# Display_Roll.net
KiCad netlist of a schematic drawn in Altium Designer
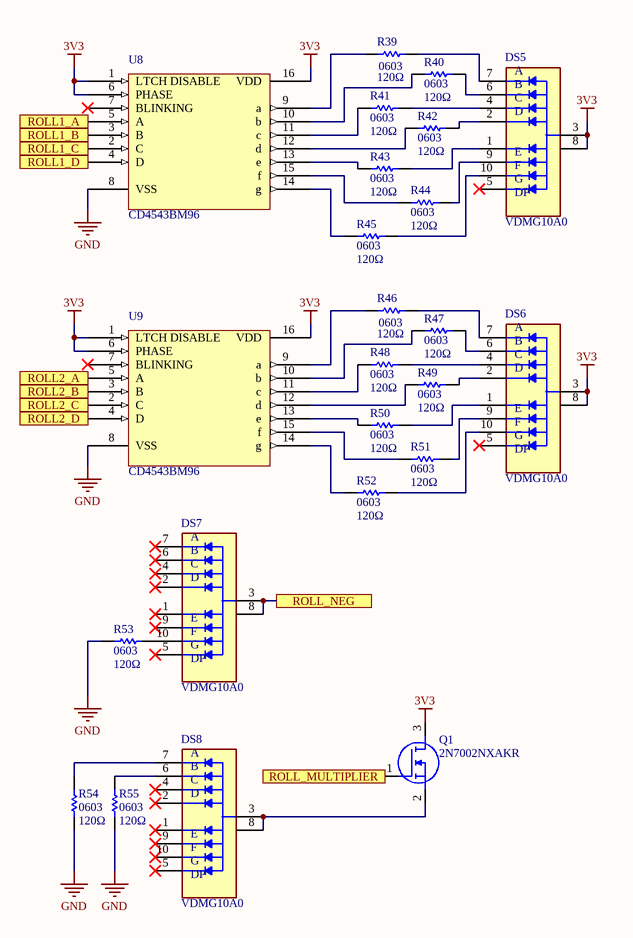
[diagram p0: Display Roll.SchDoc]

(export (version "E")
  (design (tool "Eeschema 10.0.6"))
  (components
    (comp (ref "DS5")
      (value "VDMG10A0")
      (footprint "DISPLAY_VDMG10A0")
      (description "Smart/Normal 7 Seg Numeric LED Display")
      (fields (field (name "MANUFACTURER") "Vishay Semiconductors"))
      (libsource (lib "SKALE_LIB") (part "7 SEG DISPLAY - VDMG10A0"))
    )
    (comp (ref "DS6")
      (value "VDMG10A0")
      (footprint "DISPLAY_VDMG10A0")
      (description "Smart/Normal 7 Seg Numeric LED Display")
      (fields (field (name "MANUFACTURER") "Vishay Semiconductors"))
      (libsource (lib "SKALE_LIB") (part "7 SEG DISPLAY - VDMG10A0"))
    )
    (comp (ref "DS7")
      (value "VDMG10A0")
      (footprint "DISPLAY_VDMG10A0")
      (description "Smart/Normal 7 Seg Numeric LED Display")
      (fields (field (name "MANUFACTURER") "Vishay Semiconductors"))
      (libsource (lib "SKALE_LIB") (part "7 SEG DISPLAY - VDMG10A0"))
    )
    (comp (ref "DS8")
      (value "VDMG10A0")
      (footprint "DISPLAY_VDMG10A0")
      (description "Smart/Normal 7 Seg Numeric LED Display")
      (fields (field (name "MANUFACTURER") "Vishay Semiconductors"))
      (libsource (lib "SKALE_LIB") (part "7 SEG DISPLAY - VDMG10A0"))
    )
    (comp (ref "Q1")
      (value "2N7002NXAKR")
      (footprint "SKALE_LIB:TO-236AB")
      (description "Transistor Mosfet N-ch 60V 0.3A 3-PIN TO-263AB T/r")
      (fields (field (name "MF") "Nexperia USA Inc.") (field (name "MANUFACTURER") "Nexperia"))
      (libsource (lib "SKALE_LIB") (part "MOSFET N-60V-190mA"))
    )
    (comp (ref "R39")
      (value "120Ω")
      (footprint "RES0603")
      (description "RES 120 OHM 5% 1/10W 0603")
      (fields (field (name "PACKAGE/FOOTPRINT") "0603") (field (name "Comment") "RES_120Ω_0603"))
      (libsource (lib "SKALE_LIB") (part "RES_120Ω_0603_5%"))
    )
    (comp (ref "R40")
      (value "120Ω")
      (footprint "RES0603")
      (description "RES 120 OHM 5% 1/10W 0603")
      (fields (field (name "PACKAGE/FOOTPRINT") "0603") (field (name "Comment") "RES_120Ω_0603"))
      (libsource (lib "SKALE_LIB") (part "RES_120Ω_0603_5%"))
    )
    (comp (ref "R41")
      (value "120Ω")
      (footprint "RES0603")
      (description "RES 120 OHM 5% 1/10W 0603")
      (fields (field (name "PACKAGE/FOOTPRINT") "0603") (field (name "Comment") "RES_120Ω_0603"))
      (libsource (lib "SKALE_LIB") (part "RES_120Ω_0603_5%"))
    )
    (comp (ref "R42")
      (value "120Ω")
      (footprint "RES0603")
      (description "RES 120 OHM 5% 1/10W 0603")
      (fields (field (name "PACKAGE/FOOTPRINT") "0603") (field (name "Comment") "RES_120Ω_0603"))
      (libsource (lib "SKALE_LIB") (part "RES_120Ω_0603_5%"))
    )
    (comp (ref "R43")
      (value "120Ω")
      (footprint "RES0603")
      (description "RES 120 OHM 5% 1/10W 0603")
      (fields (field (name "PACKAGE/FOOTPRINT") "0603") (field (name "Comment") "RES_120Ω_0603"))
      (libsource (lib "SKALE_LIB") (part "RES_120Ω_0603_5%"))
    )
    (comp (ref "R44")
      (value "120Ω")
      (footprint "RES0603")
      (description "RES 120 OHM 5% 1/10W 0603")
      (fields (field (name "PACKAGE/FOOTPRINT") "0603") (field (name "Comment") "RES_120Ω_0603"))
      (libsource (lib "SKALE_LIB") (part "RES_120Ω_0603_5%"))
    )
    (comp (ref "R45")
      (value "120Ω")
      (footprint "RES0603")
      (description "RES 120 OHM 5% 1/10W 0603")
      (fields (field (name "PACKAGE/FOOTPRINT") "0603") (field (name "Comment") "RES_120Ω_0603"))
      (libsource (lib "SKALE_LIB") (part "RES_120Ω_0603_5%"))
    )
    (comp (ref "R46")
      (value "120Ω")
      (footprint "RES0603")
      (description "RES 120 OHM 5% 1/10W 0603")
      (fields (field (name "PACKAGE/FOOTPRINT") "0603") (field (name "Comment") "RES_120Ω_0603"))
      (libsource (lib "SKALE_LIB") (part "RES_120Ω_0603_5%"))
    )
    (comp (ref "R47")
      (value "120Ω")
      (footprint "RES0603")
      (description "RES 120 OHM 5% 1/10W 0603")
      (fields (field (name "PACKAGE/FOOTPRINT") "0603") (field (name "Comment") "RES_120Ω_0603"))
      (libsource (lib "SKALE_LIB") (part "RES_120Ω_0603_5%"))
    )
    (comp (ref "R48")
      (value "120Ω")
      (footprint "RES0603")
      (description "RES 120 OHM 5% 1/10W 0603")
      (fields (field (name "PACKAGE/FOOTPRINT") "0603") (field (name "Comment") "RES_120Ω_0603"))
      (libsource (lib "SKALE_LIB") (part "RES_120Ω_0603_5%"))
    )
    (comp (ref "R49")
      (value "120Ω")
      (footprint "RES0603")
      (description "RES 120 OHM 5% 1/10W 0603")
      (fields (field (name "PACKAGE/FOOTPRINT") "0603") (field (name "Comment") "RES_120Ω_0603"))
      (libsource (lib "SKALE_LIB") (part "RES_120Ω_0603_5%"))
    )
    (comp (ref "R50")
      (value "120Ω")
      (footprint "RES0603")
      (description "RES 120 OHM 5% 1/10W 0603")
      (fields (field (name "PACKAGE/FOOTPRINT") "0603") (field (name "Comment") "RES_120Ω_0603"))
      (libsource (lib "SKALE_LIB") (part "RES_120Ω_0603_5%"))
    )
    (comp (ref "R51")
      (value "120Ω")
      (footprint "RES0603")
      (description "RES 120 OHM 5% 1/10W 0603")
      (fields (field (name "PACKAGE/FOOTPRINT") "0603") (field (name "Comment") "RES_120Ω_0603"))
      (libsource (lib "SKALE_LIB") (part "RES_120Ω_0603_5%"))
    )
    (comp (ref "R52")
      (value "120Ω")
      (footprint "RES0603")
      (description "RES 120 OHM 5% 1/10W 0603")
      (fields (field (name "PACKAGE/FOOTPRINT") "0603") (field (name "Comment") "RES_120Ω_0603"))
      (libsource (lib "SKALE_LIB") (part "RES_120Ω_0603_5%"))
    )
    (comp (ref "R53")
      (value "120Ω")
      (footprint "RES0603")
      (description "RES 120 OHM 5% 1/10W 0603")
      (fields (field (name "PACKAGE/FOOTPRINT") "0603") (field (name "Comment") "RES_120Ω_0603"))
      (libsource (lib "SKALE_LIB") (part "RES_120Ω_0603_5%"))
    )
    (comp (ref "R54")
      (value "120Ω")
      (footprint "RES0603")
      (description "RES 120 OHM 5% 1/10W 0603")
      (fields (field (name "PACKAGE/FOOTPRINT") "0603") (field (name "Comment") "RES_120Ω_0603"))
      (libsource (lib "SKALE_LIB") (part "RES_120Ω_0603_5%"))
    )
    (comp (ref "R55")
      (value "120Ω")
      (footprint "RES0603")
      (description "RES 120 OHM 5% 1/10W 0603")
      (fields (field (name "PACKAGE/FOOTPRINT") "0603") (field (name "Comment") "RES_120Ω_0603"))
      (libsource (lib "SKALE_LIB") (part "RES_120Ω_0603_5%"))
    )
    (comp (ref "U8")
      (value "CD4543BM96")
      (footprint "SOIC127P600X175-16N")
      (description "Seven Segment Decoder/Driver, 4000/14000/40000 Series, Configurable Output, CMOS, PDSO16")
      (fields (field (name "MANUFACTURER") "Texas Instruments"))
      (libsource (lib "SKALE_LIB") (part "7 SEG DISPLAY IC"))
    )
    (comp (ref "U9")
      (value "CD4543BM96")
      (footprint "SOIC127P600X175-16N")
      (description "Seven Segment Decoder/Driver, 4000/14000/40000 Series, Configurable Output, CMOS, PDSO16")
      (fields (field (name "MANUFACTURER") "Texas Instruments"))
      (libsource (lib "SKALE_LIB") (part "7 SEG DISPLAY IC"))
    )
  )
  (nets
    (net (code "1") (name "/ROLL1_A") (class "Default")
      (node (ref "U8") (pin "5") (pinfunction "A_5") (pintype "input"))
    )
    (net (code "2") (name "/ROLL1_B") (class "Default")
      (node (ref "U8") (pin "3") (pinfunction "B_3") (pintype "input"))
    )
    (net (code "3") (name "/ROLL1_C") (class "Default")
      (node (ref "U8") (pin "2") (pinfunction "C_2") (pintype "input"))
    )
    (net (code "4") (name "/ROLL1_D") (class "Default")
      (node (ref "U8") (pin "4") (pinfunction "D_4") (pintype "input"))
    )
    (net (code "5") (name "/ROLL2_A") (class "Default")
      (node (ref "U9") (pin "5") (pinfunction "A_5") (pintype "input"))
    )
    (net (code "6") (name "/ROLL2_B") (class "Default")
      (node (ref "U9") (pin "3") (pinfunction "B_3") (pintype "input"))
    )
    (net (code "7") (name "/ROLL2_C") (class "Default")
      (node (ref "U9") (pin "2") (pinfunction "C_2") (pintype "input"))
    )
    (net (code "8") (name "/ROLL2_D") (class "Default")
      (node (ref "U9") (pin "4") (pinfunction "D_4") (pintype "input"))
    )
    (net (code "9") (name "/ROLL_MULTIPLIER") (class "Default")
      (node (ref "Q1") (pin "1") (pinfunction "G_1") (pintype "bidirectional"))
    )
    (net (code "10") (name "/ROLL_NEG") (class "Default")
      (node (ref "DS7") (pin "3") (pinfunction "ANODE_3") (pintype "passive"))
      (node (ref "DS7") (pin "8") (pinfunction "ANODE_8") (pintype "passive"))
    )
    (net (code "11") (name "3V3") (class "Default")
      (node (ref "DS5") (pin "3") (pinfunction "ANODE_3") (pintype "passive"))
      (node (ref "DS5") (pin "8") (pinfunction "ANODE_8") (pintype "passive"))
      (node (ref "DS6") (pin "3") (pinfunction "ANODE_3") (pintype "passive"))
      (node (ref "DS6") (pin "8") (pinfunction "ANODE_8") (pintype "passive"))
      (node (ref "Q1") (pin "3") (pinfunction "D_3") (pintype "bidirectional"))
      (node (ref "U8") (pin "1") (pinfunction "LTCH_DISABLE_1") (pintype "input"))
      (node (ref "U8") (pin "16") (pinfunction "VDD_16") (pintype "power_in"))
      (node (ref "U8") (pin "6") (pinfunction "PHASE_6") (pintype "input"))
      (node (ref "U9") (pin "1") (pinfunction "LTCH_DISABLE_1") (pintype "input"))
      (node (ref "U9") (pin "16") (pinfunction "VDD_16") (pintype "power_in"))
      (node (ref "U9") (pin "6") (pinfunction "PHASE_6") (pintype "input"))
    )
    (net (code "12") (name "GND") (class "Default")
      (node (ref "R53") (pin "1") (pinfunction "1_1") (pintype "passive"))
      (node (ref "R54") (pin "1") (pinfunction "1_1") (pintype "passive"))
      (node (ref "R55") (pin "1") (pinfunction "1_1") (pintype "passive"))
      (node (ref "U8") (pin "8") (pinfunction "VSS_8") (pintype "power_in"))
      (node (ref "U9") (pin "8") (pinfunction "VSS_8") (pintype "power_in"))
    )
    (net (code "13") (name "Net-(DS5-A)") (class "Default")
      (node (ref "DS5") (pin "7") (pinfunction "A_7") (pintype "passive"))
      (node (ref "R39") (pin "2") (pinfunction "2_2") (pintype "passive"))
    )
    (net (code "14") (name "Net-(DS5-B)") (class "Default")
      (node (ref "DS5") (pin "6") (pinfunction "B_6") (pintype "passive"))
      (node (ref "R40") (pin "2") (pinfunction "2_2") (pintype "passive"))
    )
    (net (code "15") (name "Net-(DS5-C)") (class "Default")
      (node (ref "DS5") (pin "4") (pinfunction "C_4") (pintype "passive"))
      (node (ref "R41") (pin "2") (pinfunction "2_2") (pintype "passive"))
    )
    (net (code "16") (name "Net-(DS5-D)") (class "Default")
      (node (ref "DS5") (pin "2") (pinfunction "D_2") (pintype "passive"))
      (node (ref "R42") (pin "2") (pinfunction "2_2") (pintype "passive"))
    )
    (net (code "17") (name "Net-(DS5-E)") (class "Default")
      (node (ref "DS5") (pin "1") (pinfunction "E_1") (pintype "passive"))
      (node (ref "R43") (pin "2") (pinfunction "2_2") (pintype "passive"))
    )
    (net (code "18") (name "Net-(DS5-F)") (class "Default")
      (node (ref "DS5") (pin "9") (pinfunction "F_9") (pintype "passive"))
      (node (ref "R44") (pin "2") (pinfunction "2_2") (pintype "passive"))
    )
    (net (code "19") (name "Net-(DS5-G)") (class "Default")
      (node (ref "DS5") (pin "10") (pinfunction "G_10") (pintype "passive"))
      (node (ref "R45") (pin "2") (pinfunction "2_2") (pintype "passive"))
    )
    (net (code "20") (name "Net-(DS6-A)") (class "Default")
      (node (ref "DS6") (pin "7") (pinfunction "A_7") (pintype "passive"))
      (node (ref "R46") (pin "2") (pinfunction "2_2") (pintype "passive"))
    )
    (net (code "21") (name "Net-(DS6-B)") (class "Default")
      (node (ref "DS6") (pin "6") (pinfunction "B_6") (pintype "passive"))
      (node (ref "R47") (pin "2") (pinfunction "2_2") (pintype "passive"))
    )
    (net (code "22") (name "Net-(DS6-C)") (class "Default")
      (node (ref "DS6") (pin "4") (pinfunction "C_4") (pintype "passive"))
      (node (ref "R48") (pin "2") (pinfunction "2_2") (pintype "passive"))
    )
    (net (code "23") (name "Net-(DS6-D)") (class "Default")
      (node (ref "DS6") (pin "2") (pinfunction "D_2") (pintype "passive"))
      (node (ref "R49") (pin "2") (pinfunction "2_2") (pintype "passive"))
    )
    (net (code "24") (name "Net-(DS6-E)") (class "Default")
      (node (ref "DS6") (pin "1") (pinfunction "E_1") (pintype "passive"))
      (node (ref "R50") (pin "2") (pinfunction "2_2") (pintype "passive"))
    )
    (net (code "25") (name "Net-(DS6-F)") (class "Default")
      (node (ref "DS6") (pin "9") (pinfunction "F_9") (pintype "passive"))
      (node (ref "R51") (pin "2") (pinfunction "2_2") (pintype "passive"))
    )
    (net (code "26") (name "Net-(DS6-G)") (class "Default")
      (node (ref "DS6") (pin "10") (pinfunction "G_10") (pintype "passive"))
      (node (ref "R52") (pin "2") (pinfunction "2_2") (pintype "passive"))
    )
    (net (code "27") (name "Net-(DS7-G)") (class "Default")
      (node (ref "DS7") (pin "10") (pinfunction "G_10") (pintype "passive"))
      (node (ref "R53") (pin "2") (pinfunction "2_2") (pintype "passive"))
    )
    (net (code "28") (name "Net-(DS8-A)") (class "Default")
      (node (ref "DS8") (pin "7") (pinfunction "A_7") (pintype "passive"))
      (node (ref "R54") (pin "2") (pinfunction "2_2") (pintype "passive"))
    )
    (net (code "29") (name "Net-(DS8-B)") (class "Default")
      (node (ref "DS8") (pin "6") (pinfunction "B_6") (pintype "passive"))
      (node (ref "R55") (pin "2") (pinfunction "2_2") (pintype "passive"))
    )
    (net (code "30") (name "Net-(Q1-S)") (class "Default")
      (node (ref "DS8") (pin "3") (pinfunction "ANODE_3") (pintype "passive"))
      (node (ref "DS8") (pin "8") (pinfunction "ANODE_8") (pintype "passive"))
      (node (ref "Q1") (pin "2") (pinfunction "S_2") (pintype "bidirectional"))
    )
    (net (code "31") (name "Net-(U8-a)") (class "Default")
      (node (ref "R39") (pin "1") (pinfunction "1_1") (pintype "passive"))
      (node (ref "U8") (pin "9") (pinfunction "a_9") (pintype "output"))
    )
    (net (code "32") (name "Net-(U8-b)") (class "Default")
      (node (ref "R40") (pin "1") (pinfunction "1_1") (pintype "passive"))
      (node (ref "U8") (pin "10") (pinfunction "b_10") (pintype "output"))
    )
    (net (code "33") (name "Net-(U8-c)") (class "Default")
      (node (ref "R41") (pin "1") (pinfunction "1_1") (pintype "passive"))
      (node (ref "U8") (pin "11") (pinfunction "c_11") (pintype "output"))
    )
    (net (code "34") (name "Net-(U8-d)") (class "Default")
      (node (ref "R42") (pin "1") (pinfunction "1_1") (pintype "passive"))
      (node (ref "U8") (pin "12") (pinfunction "d_12") (pintype "output"))
    )
    (net (code "35") (name "Net-(U8-e)") (class "Default")
      (node (ref "R43") (pin "1") (pinfunction "1_1") (pintype "passive"))
      (node (ref "U8") (pin "13") (pinfunction "e_13") (pintype "output"))
    )
    (net (code "36") (name "Net-(U8-f)") (class "Default")
      (node (ref "R44") (pin "1") (pinfunction "1_1") (pintype "passive"))
      (node (ref "U8") (pin "15") (pinfunction "f_15") (pintype "output"))
    )
    (net (code "37") (name "Net-(U8-g)") (class "Default")
      (node (ref "R45") (pin "1") (pinfunction "1_1") (pintype "passive"))
      (node (ref "U8") (pin "14") (pinfunction "g_14") (pintype "output"))
    )
    (net (code "38") (name "Net-(U9-a)") (class "Default")
      (node (ref "R46") (pin "1") (pinfunction "1_1") (pintype "passive"))
      (node (ref "U9") (pin "9") (pinfunction "a_9") (pintype "output"))
    )
    (net (code "39") (name "Net-(U9-b)") (class "Default")
      (node (ref "R47") (pin "1") (pinfunction "1_1") (pintype "passive"))
      (node (ref "U9") (pin "10") (pinfunction "b_10") (pintype "output"))
    )
    (net (code "40") (name "Net-(U9-c)") (class "Default")
      (node (ref "R48") (pin "1") (pinfunction "1_1") (pintype "passive"))
      (node (ref "U9") (pin "11") (pinfunction "c_11") (pintype "output"))
    )
    (net (code "41") (name "Net-(U9-d)") (class "Default")
      (node (ref "R49") (pin "1") (pinfunction "1_1") (pintype "passive"))
      (node (ref "U9") (pin "12") (pinfunction "d_12") (pintype "output"))
    )
    (net (code "42") (name "Net-(U9-e)") (class "Default")
      (node (ref "R50") (pin "1") (pinfunction "1_1") (pintype "passive"))
      (node (ref "U9") (pin "13") (pinfunction "e_13") (pintype "output"))
    )
    (net (code "43") (name "Net-(U9-f)") (class "Default")
      (node (ref "R51") (pin "1") (pinfunction "1_1") (pintype "passive"))
      (node (ref "U9") (pin "15") (pinfunction "f_15") (pintype "output"))
    )
    (net (code "44") (name "Net-(U9-g)") (class "Default")
      (node (ref "R52") (pin "1") (pinfunction "1_1") (pintype "passive"))
      (node (ref "U9") (pin "14") (pinfunction "g_14") (pintype "output"))
    )
    (net (code "45") (name "unconnected-(DS5-DP-Pad5)") (class "Default")
      (node (ref "DS5") (pin "5") (pinfunction "DP_5") (pintype "passive+no_connect"))
    )
    (net (code "46") (name "unconnected-(DS6-DP-Pad5)") (class "Default")
      (node (ref "DS6") (pin "5") (pinfunction "DP_5") (pintype "passive+no_connect"))
    )
    (net (code "47") (name "unconnected-(DS7-A-Pad7)") (class "Default")
      (node (ref "DS7") (pin "7") (pinfunction "A_7") (pintype "passive+no_connect"))
    )
    (net (code "48") (name "unconnected-(DS7-B-Pad6)") (class "Default")
      (node (ref "DS7") (pin "6") (pinfunction "B_6") (pintype "passive+no_connect"))
    )
    (net (code "49") (name "unconnected-(DS7-C-Pad4)") (class "Default")
      (node (ref "DS7") (pin "4") (pinfunction "C_4") (pintype "passive+no_connect"))
    )
    (net (code "50") (name "unconnected-(DS7-D-Pad2)") (class "Default")
      (node (ref "DS7") (pin "2") (pinfunction "D_2") (pintype "passive+no_connect"))
    )
    (net (code "51") (name "unconnected-(DS7-DP-Pad5)") (class "Default")
      (node (ref "DS7") (pin "5") (pinfunction "DP_5") (pintype "passive+no_connect"))
    )
    (net (code "52") (name "unconnected-(DS7-E-Pad1)") (class "Default")
      (node (ref "DS7") (pin "1") (pinfunction "E_1") (pintype "passive+no_connect"))
    )
    (net (code "53") (name "unconnected-(DS7-F-Pad9)") (class "Default")
      (node (ref "DS7") (pin "9") (pinfunction "F_9") (pintype "passive+no_connect"))
    )
    (net (code "54") (name "unconnected-(DS8-C-Pad4)") (class "Default")
      (node (ref "DS8") (pin "4") (pinfunction "C_4") (pintype "passive+no_connect"))
    )
    (net (code "55") (name "unconnected-(DS8-D-Pad2)") (class "Default")
      (node (ref "DS8") (pin "2") (pinfunction "D_2") (pintype "passive+no_connect"))
    )
    (net (code "56") (name "unconnected-(DS8-DP-Pad5)") (class "Default")
      (node (ref "DS8") (pin "5") (pinfunction "DP_5") (pintype "passive+no_connect"))
    )
    (net (code "57") (name "unconnected-(DS8-E-Pad1)") (class "Default")
      (node (ref "DS8") (pin "1") (pinfunction "E_1") (pintype "passive+no_connect"))
    )
    (net (code "58") (name "unconnected-(DS8-F-Pad9)") (class "Default")
      (node (ref "DS8") (pin "9") (pinfunction "F_9") (pintype "passive+no_connect"))
    )
    (net (code "59") (name "unconnected-(DS8-G-Pad10)") (class "Default")
      (node (ref "DS8") (pin "10") (pinfunction "G_10") (pintype "passive+no_connect"))
    )
    (net (code "60") (name "unconnected-(U8-BLINKING-Pad7)") (class "Default")
      (node (ref "U8") (pin "7") (pinfunction "BLINKING_7") (pintype "input+no_connect"))
    )
    (net (code "61") (name "unconnected-(U9-BLINKING-Pad7)") (class "Default")
      (node (ref "U9") (pin "7") (pinfunction "BLINKING_7") (pintype "input+no_connect"))
    )
  )
)
